# DA-2000.net
KiCad netlist of a schematic drawn in EAGLE
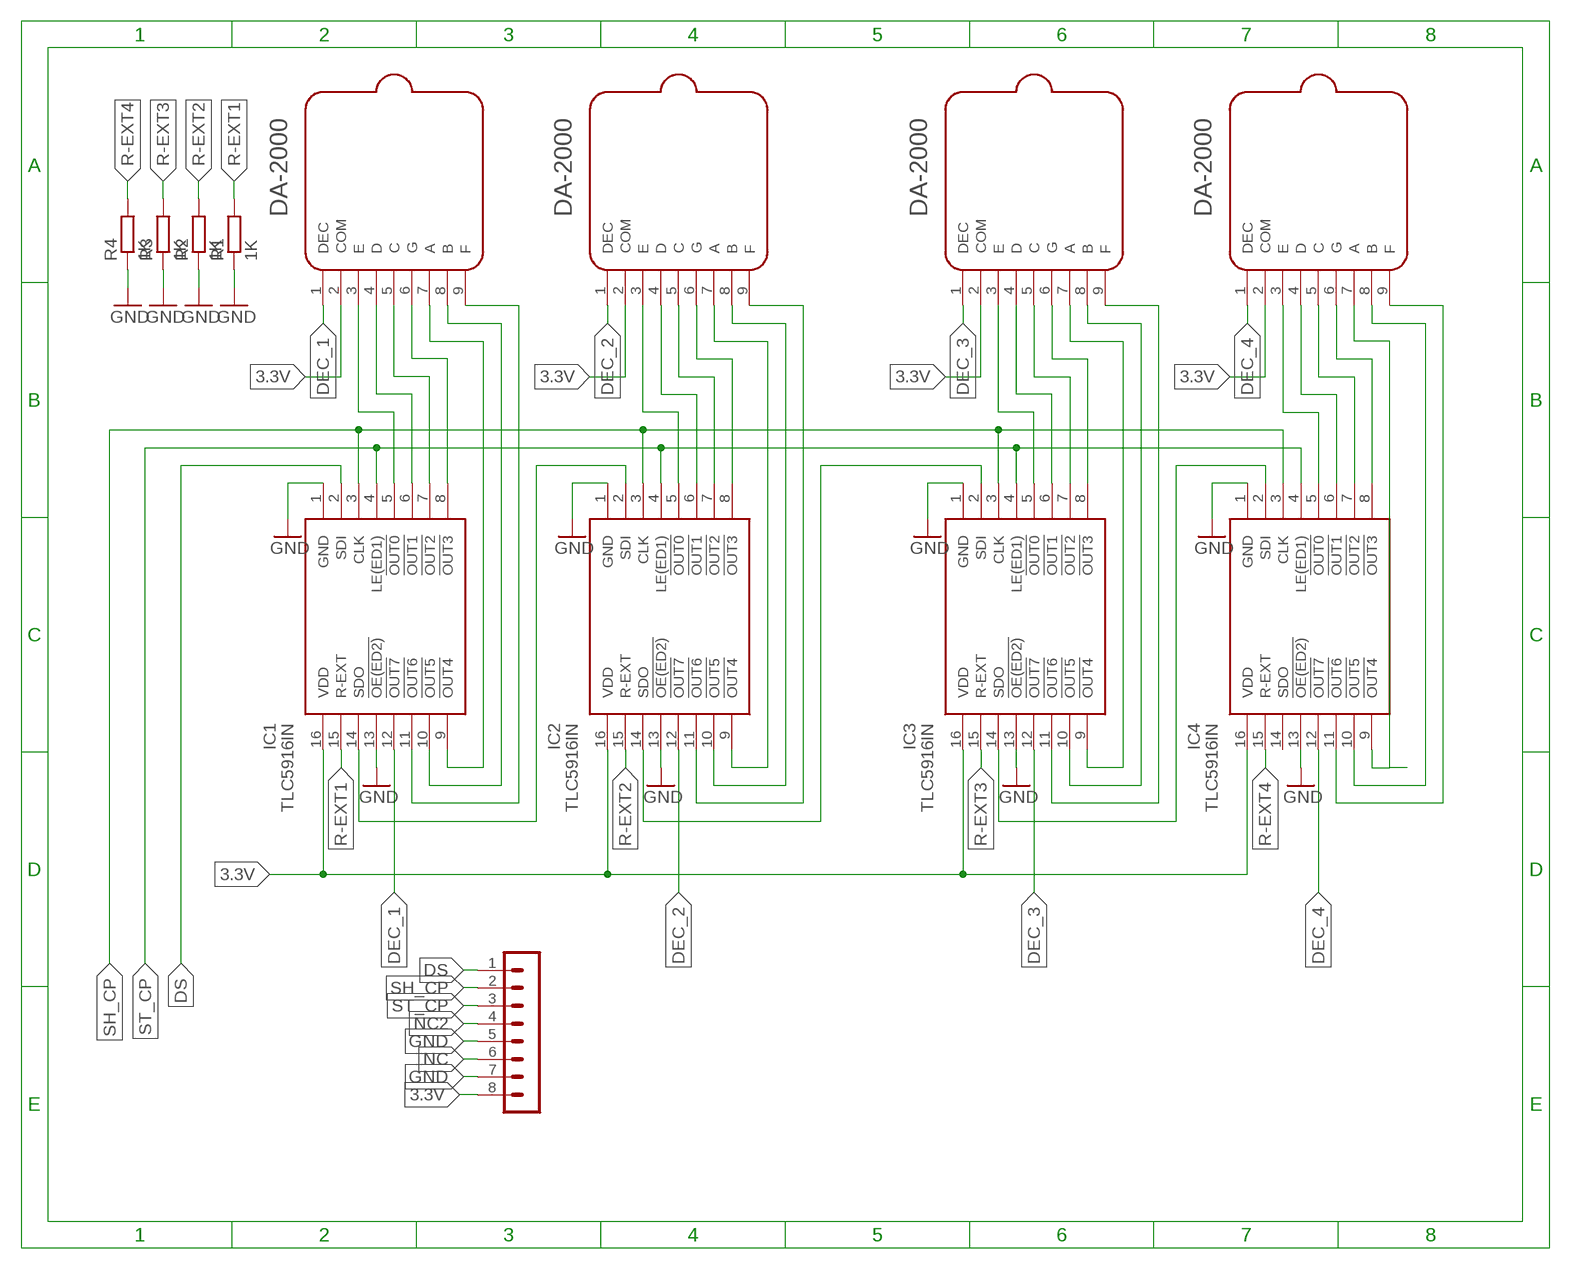
[diagram p0: schematic, sheet 1]

(export (version "E")
  (design (tool "Eeschema 10.0.6"))
  (components
    (comp (ref "IC1")
      (value "TLC5916IN")
      (footprint "eagle-import:DIP794W53P254L1930H508Q16N")
      (fields (field (name "MOUSER_PART_NUMBER") "595-TLC5916IN"))
      (libsource (lib "eagle-import") (part "TLC5916IN"))
    )
    (comp (ref "IC2")
      (value "TLC5916IN")
      (footprint "eagle-import:DIP794W53P254L1930H508Q16N")
      (fields (field (name "MOUSER_PART_NUMBER") "595-TLC5916IN"))
      (libsource (lib "eagle-import") (part "TLC5916IN"))
    )
    (comp (ref "IC3")
      (value "TLC5916IN")
      (footprint "eagle-import:DIP794W53P254L1930H508Q16N")
      (fields (field (name "MOUSER_PART_NUMBER") "595-TLC5916IN"))
      (libsource (lib "eagle-import") (part "TLC5916IN"))
    )
    (comp (ref "IC4")
      (value "TLC5916IN")
      (footprint "eagle-import:DIP794W53P254L1930H508Q16N")
      (fields (field (name "MOUSER_PART_NUMBER") "595-TLC5916IN"))
      (libsource (lib "eagle-import") (part "TLC5916IN"))
    )
    (comp (ref "R1")
      (value "1K")
      (footprint "eagle-import:R1206")
      (libsource (lib "eagle-import") (part "R-EU_R1206"))
    )
    (comp (ref "R2")
      (value "1K")
      (footprint "eagle-import:R1206")
      (libsource (lib "eagle-import") (part "R-EU_R1206"))
    )
    (comp (ref "R3")
      (value "1K")
      (footprint "eagle-import:R1206")
      (libsource (lib "eagle-import") (part "R-EU_R1206"))
    )
    (comp (ref "R4")
      (value "1K")
      (footprint "eagle-import:R1206")
      (libsource (lib "eagle-import") (part "R-EU_R1206"))
    )
    (comp (ref "SV2")
      (value "PINHEADER-1X8")
      (footprint "eagle-import:MA08-1")
      (libsource (lib "eagle-import") (part "PINHEADER-1X8"))
    )
    (comp (ref "U$1")
      (value "DA-2000")
      (footprint "eagle-import:DA-2000")
      (libsource (lib "eagle-import") (part "DA-2000"))
    )
    (comp (ref "U$2")
      (value "DA-2000")
      (footprint "eagle-import:DA-2000")
      (libsource (lib "eagle-import") (part "DA-2000"))
    )
    (comp (ref "U$3")
      (value "DA-2000")
      (footprint "eagle-import:DA-2000")
      (libsource (lib "eagle-import") (part "DA-2000"))
    )
    (comp (ref "U$4")
      (value "DA-2000")
      (footprint "eagle-import:DA-2000")
      (libsource (lib "eagle-import") (part "DA-2000"))
    )
  )
  (nets
    (net (code "1") (name "3.3V") (class "Default")
      (node (ref "IC1") (pin "16") (pinfunction "VDD_16") (pintype "bidirectional"))
      (node (ref "IC2") (pin "16") (pinfunction "VDD_16") (pintype "bidirectional"))
      (node (ref "IC3") (pin "16") (pinfunction "VDD_16") (pintype "bidirectional"))
      (node (ref "IC4") (pin "16") (pinfunction "VDD_16") (pintype "bidirectional"))
      (node (ref "SV2") (pin "8") (pinfunction "8_8") (pintype "passive"))
      (node (ref "U$1") (pin "2") (pinfunction "COM_2") (pintype "power_in"))
      (node (ref "U$2") (pin "2") (pinfunction "COM_2") (pintype "power_in"))
      (node (ref "U$3") (pin "2") (pinfunction "COM_2") (pintype "power_in"))
      (node (ref "U$4") (pin "2") (pinfunction "COM_2") (pintype "power_in"))
    )
    (net (code "2") (name "DEC_1") (class "Default")
      (node (ref "IC1") (pin "12") (pinfunction "~{OUT7}_12") (pintype "bidirectional"))
      (node (ref "U$1") (pin "1") (pinfunction "DEC_1") (pintype "input"))
    )
    (net (code "3") (name "DEC_2") (class "Default")
      (node (ref "IC2") (pin "12") (pinfunction "~{OUT7}_12") (pintype "bidirectional"))
      (node (ref "U$2") (pin "1") (pinfunction "DEC_1") (pintype "input"))
    )
    (net (code "4") (name "DEC_3") (class "Default")
      (node (ref "IC3") (pin "12") (pinfunction "~{OUT7}_12") (pintype "bidirectional"))
      (node (ref "U$3") (pin "1") (pinfunction "DEC_1") (pintype "input"))
    )
    (net (code "5") (name "DEC_4") (class "Default")
      (node (ref "IC4") (pin "12") (pinfunction "~{OUT7}_12") (pintype "bidirectional"))
      (node (ref "U$4") (pin "1") (pinfunction "DEC_1") (pintype "input"))
    )
    (net (code "6") (name "DS") (class "Default")
      (node (ref "IC1") (pin "2") (pinfunction "SDI_2") (pintype "bidirectional"))
      (node (ref "SV2") (pin "1") (pinfunction "1_1") (pintype "passive"))
    )
    (net (code "7") (name "GND") (class "Default")
      (node (ref "IC1") (pin "1") (pinfunction "GND_1") (pintype "bidirectional"))
      (node (ref "IC1") (pin "13") (pinfunction "~{OE(ED2})_13") (pintype "bidirectional"))
      (node (ref "IC2") (pin "1") (pinfunction "GND_1") (pintype "bidirectional"))
      (node (ref "IC2") (pin "13") (pinfunction "~{OE(ED2})_13") (pintype "bidirectional"))
      (node (ref "IC3") (pin "1") (pinfunction "GND_1") (pintype "bidirectional"))
      (node (ref "IC3") (pin "13") (pinfunction "~{OE(ED2})_13") (pintype "bidirectional"))
      (node (ref "IC4") (pin "1") (pinfunction "GND_1") (pintype "bidirectional"))
      (node (ref "IC4") (pin "13") (pinfunction "~{OE(ED2})_13") (pintype "bidirectional"))
      (node (ref "R1") (pin "1") (pinfunction "1_1") (pintype "passive"))
      (node (ref "R2") (pin "1") (pinfunction "1_1") (pintype "passive"))
      (node (ref "R3") (pin "1") (pinfunction "1_1") (pintype "passive"))
      (node (ref "R4") (pin "1") (pinfunction "1_1") (pintype "passive"))
      (node (ref "SV2") (pin "5") (pinfunction "5_5") (pintype "passive"))
      (node (ref "SV2") (pin "7") (pinfunction "7_7") (pintype "passive"))
    )
    (net (code "8") (name "NC") (class "Default")
      (node (ref "SV2") (pin "6") (pinfunction "6_6") (pintype "passive"))
    )
    (net (code "9") (name "NC2") (class "Default")
      (node (ref "SV2") (pin "4") (pinfunction "4_4") (pintype "passive"))
    )
    (net (code "10") (name "Net-(IC1-SDO)") (class "Default")
      (node (ref "IC1") (pin "14") (pinfunction "SDO_14") (pintype "bidirectional"))
      (node (ref "IC2") (pin "2") (pinfunction "SDI_2") (pintype "bidirectional"))
    )
    (net (code "11") (name "Net-(IC1-~{OUT0})") (class "Default")
      (node (ref "IC1") (pin "5") (pinfunction "~{OUT0}_5") (pintype "bidirectional"))
      (node (ref "U$1") (pin "3") (pinfunction "E_3") (pintype "input"))
    )
    (net (code "12") (name "Net-(IC1-~{OUT1})") (class "Default")
      (node (ref "IC1") (pin "6") (pinfunction "~{OUT1}_6") (pintype "bidirectional"))
      (node (ref "U$1") (pin "4") (pinfunction "D_4") (pintype "input"))
    )
    (net (code "13") (name "Net-(IC1-~{OUT2})") (class "Default")
      (node (ref "IC1") (pin "7") (pinfunction "~{OUT2}_7") (pintype "bidirectional"))
      (node (ref "U$1") (pin "5") (pinfunction "C_5") (pintype "input"))
    )
    (net (code "14") (name "Net-(IC1-~{OUT3})") (class "Default")
      (node (ref "IC1") (pin "8") (pinfunction "~{OUT3}_8") (pintype "bidirectional"))
      (node (ref "U$1") (pin "6") (pinfunction "G_6") (pintype "input"))
    )
    (net (code "15") (name "Net-(IC1-~{OUT4})") (class "Default")
      (node (ref "IC1") (pin "9") (pinfunction "~{OUT4}_9") (pintype "bidirectional"))
      (node (ref "U$1") (pin "7") (pinfunction "A_7") (pintype "input"))
    )
    (net (code "16") (name "Net-(IC1-~{OUT5})") (class "Default")
      (node (ref "IC1") (pin "10") (pinfunction "~{OUT5}_10") (pintype "bidirectional"))
      (node (ref "U$1") (pin "8") (pinfunction "B_8") (pintype "input"))
    )
    (net (code "17") (name "Net-(IC1-~{OUT6})") (class "Default")
      (node (ref "IC1") (pin "11") (pinfunction "~{OUT6}_11") (pintype "bidirectional"))
      (node (ref "U$1") (pin "9") (pinfunction "F_9") (pintype "input"))
    )
    (net (code "18") (name "Net-(IC2-SDO)") (class "Default")
      (node (ref "IC2") (pin "14") (pinfunction "SDO_14") (pintype "bidirectional"))
      (node (ref "IC3") (pin "2") (pinfunction "SDI_2") (pintype "bidirectional"))
    )
    (net (code "19") (name "Net-(IC2-~{OUT0})") (class "Default")
      (node (ref "IC2") (pin "5") (pinfunction "~{OUT0}_5") (pintype "bidirectional"))
      (node (ref "U$2") (pin "3") (pinfunction "E_3") (pintype "input"))
    )
    (net (code "20") (name "Net-(IC2-~{OUT1})") (class "Default")
      (node (ref "IC2") (pin "6") (pinfunction "~{OUT1}_6") (pintype "bidirectional"))
      (node (ref "U$2") (pin "4") (pinfunction "D_4") (pintype "input"))
    )
    (net (code "21") (name "Net-(IC2-~{OUT2})") (class "Default")
      (node (ref "IC2") (pin "7") (pinfunction "~{OUT2}_7") (pintype "bidirectional"))
      (node (ref "U$2") (pin "5") (pinfunction "C_5") (pintype "input"))
    )
    (net (code "22") (name "Net-(IC2-~{OUT3})") (class "Default")
      (node (ref "IC2") (pin "8") (pinfunction "~{OUT3}_8") (pintype "bidirectional"))
      (node (ref "U$2") (pin "6") (pinfunction "G_6") (pintype "input"))
    )
    (net (code "23") (name "Net-(IC2-~{OUT4})") (class "Default")
      (node (ref "IC2") (pin "9") (pinfunction "~{OUT4}_9") (pintype "bidirectional"))
      (node (ref "U$2") (pin "7") (pinfunction "A_7") (pintype "input"))
    )
    (net (code "24") (name "Net-(IC2-~{OUT5})") (class "Default")
      (node (ref "IC2") (pin "10") (pinfunction "~{OUT5}_10") (pintype "bidirectional"))
      (node (ref "U$2") (pin "8") (pinfunction "B_8") (pintype "input"))
    )
    (net (code "25") (name "Net-(IC2-~{OUT6})") (class "Default")
      (node (ref "IC2") (pin "11") (pinfunction "~{OUT6}_11") (pintype "bidirectional"))
      (node (ref "U$2") (pin "9") (pinfunction "F_9") (pintype "input"))
    )
    (net (code "26") (name "Net-(IC3-SDO)") (class "Default")
      (node (ref "IC3") (pin "14") (pinfunction "SDO_14") (pintype "bidirectional"))
      (node (ref "IC4") (pin "2") (pinfunction "SDI_2") (pintype "bidirectional"))
    )
    (net (code "27") (name "Net-(IC3-~{OUT0})") (class "Default")
      (node (ref "IC3") (pin "5") (pinfunction "~{OUT0}_5") (pintype "bidirectional"))
      (node (ref "U$3") (pin "3") (pinfunction "E_3") (pintype "input"))
    )
    (net (code "28") (name "Net-(IC3-~{OUT1})") (class "Default")
      (node (ref "IC3") (pin "6") (pinfunction "~{OUT1}_6") (pintype "bidirectional"))
      (node (ref "U$3") (pin "4") (pinfunction "D_4") (pintype "input"))
    )
    (net (code "29") (name "Net-(IC3-~{OUT2})") (class "Default")
      (node (ref "IC3") (pin "7") (pinfunction "~{OUT2}_7") (pintype "bidirectional"))
      (node (ref "U$3") (pin "5") (pinfunction "C_5") (pintype "input"))
    )
    (net (code "30") (name "Net-(IC3-~{OUT3})") (class "Default")
      (node (ref "IC3") (pin "8") (pinfunction "~{OUT3}_8") (pintype "bidirectional"))
      (node (ref "U$3") (pin "6") (pinfunction "G_6") (pintype "input"))
    )
    (net (code "31") (name "Net-(IC3-~{OUT4})") (class "Default")
      (node (ref "IC3") (pin "9") (pinfunction "~{OUT4}_9") (pintype "bidirectional"))
      (node (ref "U$3") (pin "7") (pinfunction "A_7") (pintype "input"))
    )
    (net (code "32") (name "Net-(IC3-~{OUT5})") (class "Default")
      (node (ref "IC3") (pin "10") (pinfunction "~{OUT5}_10") (pintype "bidirectional"))
      (node (ref "U$3") (pin "8") (pinfunction "B_8") (pintype "input"))
    )
    (net (code "33") (name "Net-(IC3-~{OUT6})") (class "Default")
      (node (ref "IC3") (pin "11") (pinfunction "~{OUT6}_11") (pintype "bidirectional"))
      (node (ref "U$3") (pin "9") (pinfunction "F_9") (pintype "input"))
    )
    (net (code "34") (name "Net-(IC4-~{OUT0})") (class "Default")
      (node (ref "IC4") (pin "5") (pinfunction "~{OUT0}_5") (pintype "bidirectional"))
      (node (ref "U$4") (pin "3") (pinfunction "E_3") (pintype "input"))
    )
    (net (code "35") (name "Net-(IC4-~{OUT1})") (class "Default")
      (node (ref "IC4") (pin "6") (pinfunction "~{OUT1}_6") (pintype "bidirectional"))
      (node (ref "U$4") (pin "4") (pinfunction "D_4") (pintype "input"))
    )
    (net (code "36") (name "Net-(IC4-~{OUT2})") (class "Default")
      (node (ref "IC4") (pin "7") (pinfunction "~{OUT2}_7") (pintype "bidirectional"))
      (node (ref "U$4") (pin "5") (pinfunction "C_5") (pintype "input"))
    )
    (net (code "37") (name "Net-(IC4-~{OUT3})") (class "Default")
      (node (ref "IC4") (pin "8") (pinfunction "~{OUT3}_8") (pintype "bidirectional"))
      (node (ref "U$4") (pin "6") (pinfunction "G_6") (pintype "input"))
    )
    (net (code "38") (name "Net-(IC4-~{OUT4})") (class "Default")
      (node (ref "IC4") (pin "9") (pinfunction "~{OUT4}_9") (pintype "bidirectional"))
      (node (ref "U$4") (pin "7") (pinfunction "A_7") (pintype "input"))
    )
    (net (code "39") (name "Net-(IC4-~{OUT5})") (class "Default")
      (node (ref "IC4") (pin "10") (pinfunction "~{OUT5}_10") (pintype "bidirectional"))
      (node (ref "U$4") (pin "8") (pinfunction "B_8") (pintype "input"))
    )
    (net (code "40") (name "Net-(IC4-~{OUT6})") (class "Default")
      (node (ref "IC4") (pin "11") (pinfunction "~{OUT6}_11") (pintype "bidirectional"))
      (node (ref "U$4") (pin "9") (pinfunction "F_9") (pintype "input"))
    )
    (net (code "41") (name "R-EXT1") (class "Default")
      (node (ref "IC1") (pin "15") (pinfunction "R-EXT_15") (pintype "bidirectional"))
      (node (ref "R1") (pin "2") (pinfunction "2_2") (pintype "passive"))
    )
    (net (code "42") (name "R-EXT2") (class "Default")
      (node (ref "IC2") (pin "15") (pinfunction "R-EXT_15") (pintype "bidirectional"))
      (node (ref "R2") (pin "2") (pinfunction "2_2") (pintype "passive"))
    )
    (net (code "43") (name "R-EXT3") (class "Default")
      (node (ref "IC3") (pin "15") (pinfunction "R-EXT_15") (pintype "bidirectional"))
      (node (ref "R3") (pin "2") (pinfunction "2_2") (pintype "passive"))
    )
    (net (code "44") (name "R-EXT4") (class "Default")
      (node (ref "IC4") (pin "15") (pinfunction "R-EXT_15") (pintype "bidirectional"))
      (node (ref "R4") (pin "2") (pinfunction "2_2") (pintype "passive"))
    )
    (net (code "45") (name "SH_CP") (class "Default")
      (node (ref "IC1") (pin "3") (pinfunction "CLK_3") (pintype "bidirectional"))
      (node (ref "IC2") (pin "3") (pinfunction "CLK_3") (pintype "bidirectional"))
      (node (ref "IC3") (pin "3") (pinfunction "CLK_3") (pintype "bidirectional"))
      (node (ref "IC4") (pin "3") (pinfunction "CLK_3") (pintype "bidirectional"))
      (node (ref "SV2") (pin "2") (pinfunction "2_2") (pintype "passive"))
    )
    (net (code "46") (name "ST_CP") (class "Default")
      (node (ref "IC1") (pin "4") (pinfunction "LE(ED1)_4") (pintype "bidirectional"))
      (node (ref "IC2") (pin "4") (pinfunction "LE(ED1)_4") (pintype "bidirectional"))
      (node (ref "IC3") (pin "4") (pinfunction "LE(ED1)_4") (pintype "bidirectional"))
      (node (ref "IC4") (pin "4") (pinfunction "LE(ED1)_4") (pintype "bidirectional"))
      (node (ref "SV2") (pin "3") (pinfunction "3_3") (pintype "passive"))
    )
    (net (code "47") (name "unconnected-(IC4-SDO-Pad14)") (class "Default")
      (node (ref "IC4") (pin "14") (pinfunction "SDO_14") (pintype "bidirectional"))
    )
  )
)
